# GP8102STEST.net
KiCad netlist of a schematic drawn in Altium Designer
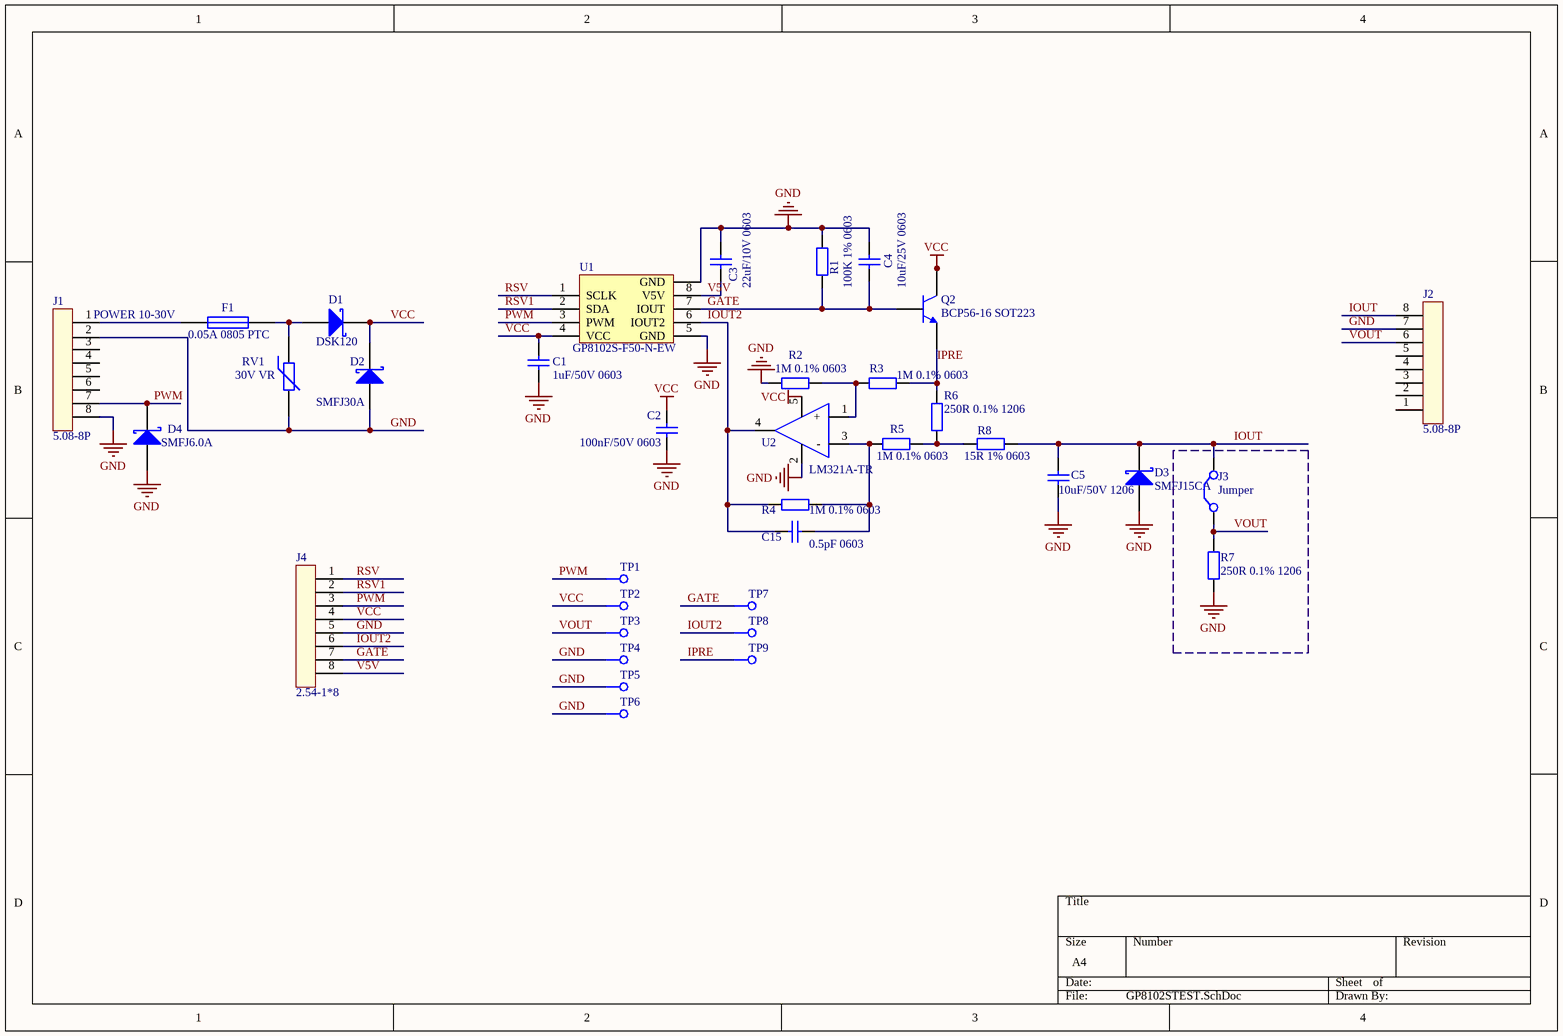
[diagram p0: GP8102STEST.SchDoc]

(export (version "E")
  (design (tool "Eeschema 10.0.6"))
  (components
    (comp (ref "C1")
      (value "1uF/50V 0603")
      (footprint "CAP_0603")
      (fields (field (name "PUBLISHER") "Altium Limited"))
      (libsource (lib "Miscellaneous Devices") (part "Cap"))
    )
    (comp (ref "C2")
      (value "100nF/50V 0603")
      (footprint "CAP_0603")
      (fields (field (name "PUBLISHER") "Altium Limited"))
      (libsource (lib "Miscellaneous Devices") (part "Cap"))
    )
    (comp (ref "C3")
      (value "22uF/10V 0603")
      (footprint "CAP_0603")
      (fields (field (name "PUBLISHER") "Altium Limited"))
      (libsource (lib "Miscellaneous Devices") (part "Cap"))
    )
    (comp (ref "C4")
      (value "10uF/25V 0603")
      (footprint "CAP_0603")
      (fields (field (name "PUBLISHER") "Altium Limited"))
      (libsource (lib "Miscellaneous Devices") (part "Cap"))
    )
    (comp (ref "C5")
      (value "10uF/50V 1206")
      (footprint "CAP_1206")
      (fields (field (name "Comment") "10nF/50V 1206") (field (name "PUBLISHER") "Altium Limited"))
      (libsource (lib "Miscellaneous Devices") (part "Cap"))
    )
    (comp (ref "C15")
      (value "0.5pF 0603")
      (footprint "CAP_0603")
      (description "1pF 0603")
      (fields (field (name "PUBLISHER") "Altium Limited"))
      (libsource (lib "Miscellaneous Devices") (part "Cap"))
    )
    (comp (ref "D1")
      (value "DSK120")
      (footprint "SODFL370X120-2N")
      (fields (field (name "PUBLISHER") "Altium Limited"))
      (libsource (lib "Miscellaneous Devices") (part "D Schottky"))
    )
    (comp (ref "D2")
      (value "SMFJ30A")
      (footprint "SODFL370X120-2N")
      (fields (field (name "PUBLISHER") "Altium Limited"))
      (libsource (lib "Miscellaneous Devices") (part "D Schottky"))
    )
    (comp (ref "D3")
      (value "SMFJ15CA")
      (footprint "SODFL370X120-2N")
      (fields (field (name "PUBLISHER") "Altium Limited"))
      (libsource (lib "Miscellaneous Devices") (part "D Schottky"))
    )
    (comp (ref "D4")
      (value "SMFJ6.0A")
      (footprint "SODFL370X120-2N")
      (fields (field (name "PUBLISHER") "Altium Limited"))
      (libsource (lib "Miscellaneous Devices") (part "D Schottky"))
    )
    (comp (ref "F1")
      (value "0.05A 0805 PTC")
      (footprint "RES_0805")
      (fields (field (name "PUBLISHER") "Altium Limited"))
      (libsource (lib "Miscellaneous Devices") (part "Fuse 1"))
    )
    (comp (ref "J1") (value "5.08-8P") (footprint "5.08-8P") (libsource (lib "SFM") (part "5.08-8P")))
    (comp (ref "J2") (value "5.08-8P") (footprint "5.08-8P") (libsource (lib "") (part "5.08-8P_2")))
    (comp (ref "J3")
      (value "Jumper")
      (footprint "2.54-1*2")
      (description "Jumper Wire")
      (fields (field (name "PUBLISHER") "Altium Limited"))
      (libsource (lib "Miscellaneous Devices") (part "Jumper"))
    )
    (comp (ref "J4")
      (value "2.54-1*8")
      (footprint "2.54-1*8")
      (description "5.08-8P")
      (libsource (lib "") (part "5.08-8P_1"))
    )
    (comp (ref "Q2")
      (value "BCP56-16 SOT223")
      (footprint "NPN_SOT223")
      (libsource (lib "SFM") (part "NPN_SOT223"))
    )
    (comp (ref "R1")
      (value "100K 1% 0603")
      (footprint "RES_0603")
      (fields (field (name "PUBLISHER") "Altium Limited"))
      (libsource (lib "") (part "Res2_1"))
    )
    (comp (ref "R2")
      (value "1M 0.1% 0603")
      (footprint "RES_0603")
      (description "1M 0603")
      (fields (field (name "PUBLISHER") "Altium Limited"))
      (libsource (lib "Miscellaneous Devices") (part "Res2"))
    )
    (comp (ref "R3")
      (value "1M 0.1% 0603")
      (footprint "RES_0603")
      (description "1M 0603")
      (fields (field (name "PUBLISHER") "Altium Limited"))
      (libsource (lib "Miscellaneous Devices") (part "Res2"))
    )
    (comp (ref "R4")
      (value "1M 0.1% 0603")
      (footprint "RES_0603")
      (description "1M 0603")
      (fields (field (name "PUBLISHER") "Altium Limited"))
      (libsource (lib "") (part "Res2_3"))
    )
    (comp (ref "R5")
      (value "1M 0.1% 0603")
      (footprint "RES_0603")
      (description "1M 0603")
      (fields (field (name "PUBLISHER") "Altium Limited"))
      (libsource (lib "Miscellaneous Devices") (part "Res2"))
    )
    (comp (ref "R6")
      (value "250R 0.1% 1206")
      (footprint "RES_1206")
      (fields (field (name "PUBLISHER") "Altium Limited"))
      (libsource (lib "") (part "Res2_2"))
    )
    (comp (ref "R7")
      (value "250R 0.1% 1206")
      (footprint "RES_1206")
      (fields (field (name "PUBLISHER") "Altium Limited"))
      (libsource (lib "") (part "Res2_2"))
    )
    (comp (ref "R8")
      (value "15R 1% 0603")
      (footprint "RES_0603")
      (description "1M 0603")
      (fields (field (name "PUBLISHER") "Altium Limited"))
      (libsource (lib "") (part "Res2_3"))
    )
    (comp (ref "RV1")
      (value "30V VR")
      (footprint "RES_0805")
      (fields (field (name "PUBLISHER") "Altium Limited"))
      (libsource (lib "Miscellaneous Devices") (part "Res Varistor"))
    )
    (comp (ref "TP1")
      (value "PWM")
      (footprint "Hole_Test")
      (description "TP")
      (libsource (lib "WXL_Integrated_Library") (part "Hole"))
    )
    (comp (ref "TP2")
      (value "VCC")
      (footprint "Hole_Test")
      (description "TP")
      (libsource (lib "WXL_Integrated_Library") (part "Hole"))
    )
    (comp (ref "TP3")
      (value "VOUT")
      (footprint "Hole_Test")
      (description "TP")
      (libsource (lib "WXL_Integrated_Library") (part "Hole"))
    )
    (comp (ref "TP4")
      (value "GND")
      (footprint "Hole_Test")
      (description "TP")
      (libsource (lib "WXL_Integrated_Library") (part "Hole"))
    )
    (comp (ref "TP5")
      (value "GND")
      (footprint "Hole_Test")
      (description "TP")
      (libsource (lib "WXL_Integrated_Library") (part "Hole"))
    )
    (comp (ref "TP6")
      (value "GND")
      (footprint "Hole_Test")
      (description "TP")
      (libsource (lib "WXL_Integrated_Library") (part "Hole"))
    )
    (comp (ref "TP7")
      (value "IOUT_7")
      (footprint "Hole_Test")
      (description "TP")
      (libsource (lib "WXL_Integrated_Library") (part "Hole"))
    )
    (comp (ref "TP8")
      (value "IOUT2")
      (footprint "Hole_Test")
      (description "TP")
      (libsource (lib "WXL_Integrated_Library") (part "Hole"))
    )
    (comp (ref "TP9")
      (value "IPRE")
      (footprint "Hole_Test")
      (description "TP")
      (libsource (lib "WXL_Integrated_Library") (part "Hole"))
    )
    (comp (ref "U1") (value "GP8102S-F50-N-EW") (footprint "ESOIC-8") (libsource (lib "SFM") (part "GP810x")))
    (comp (ref "U2")
      (value "LM321A-TR")
      (footprint "SOT23-5")
      (description "LM321 SOT23-5")
      (libsource (lib "SFM") (part "LM321"))
    )
  )
  (nets
    (net (code "1") (name "/GATE") (class "Default")
      (node (ref "C4") (pin "1") (pinfunction "1_1") (pintype "passive"))
      (node (ref "J4") (pin "7") (pintype "passive"))
      (node (ref "Q2") (pin "1") (pintype "passive"))
      (node (ref "R1") (pin "2") (pinfunction "2_2") (pintype "passive"))
      (node (ref "TP7") (pin "1") (pinfunction "SHell_1") (pintype "passive"))
      (node (ref "U1") (pin "7") (pinfunction "IOUT_7") (pintype "passive"))
    )
    (net (code "2") (name "/IOUT") (class "Default")
      (node (ref "C5") (pin "2") (pinfunction "2_2") (pintype "passive"))
      (node (ref "D3") (pin "2") (pinfunction "K_2") (pintype "passive"))
      (node (ref "J2") (pin "8") (pintype "passive"))
      (node (ref "J3") (pin "2") (pinfunction "C2_2") (pintype "passive"))
      (node (ref "R8") (pin "2") (pinfunction "2_2") (pintype "passive"))
    )
    (net (code "3") (name "/IOUT2") (class "Default")
      (node (ref "C15") (pin "1") (pinfunction "1_1") (pintype "passive"))
      (node (ref "J4") (pin "6") (pintype "passive"))
      (node (ref "R4") (pin "1") (pinfunction "1_1") (pintype "passive"))
      (node (ref "TP8") (pin "1") (pinfunction "SHell_1") (pintype "passive"))
      (node (ref "U1") (pin "6") (pinfunction "IOUT2_6") (pintype "passive"))
      (node (ref "U2") (pin "4") (pinfunction "OUTA_4") (pintype "passive"))
    )
    (net (code "4") (name "/IPRE") (class "Default")
      (node (ref "Q2") (pin "3") (pintype "passive"))
      (node (ref "R3") (pin "1") (pinfunction "1_1") (pintype "passive"))
      (node (ref "R6") (pin "2") (pinfunction "2_2") (pintype "passive"))
      (node (ref "TP9") (pin "1") (pinfunction "SHell_1") (pintype "passive"))
    )
    (net (code "5") (name "/PWM") (class "Default")
      (node (ref "D4") (pin "2") (pinfunction "K_2") (pintype "passive"))
      (node (ref "J1") (pin "7") (pintype "passive"))
      (node (ref "J4") (pin "3") (pintype "passive"))
      (node (ref "TP1") (pin "1") (pinfunction "SHell_1") (pintype "passive"))
      (node (ref "U1") (pin "3") (pinfunction "PWM_3") (pintype "passive"))
    )
    (net (code "6") (name "/RSV") (class "Default")
      (node (ref "J4") (pin "1") (pintype "passive"))
      (node (ref "U1") (pin "1") (pinfunction "SCLK_1") (pintype "passive"))
    )
    (net (code "7") (name "/RSV1") (class "Default")
      (node (ref "J4") (pin "2") (pintype "passive"))
      (node (ref "U1") (pin "2") (pinfunction "SDA_2") (pintype "passive"))
    )
    (net (code "8") (name "/V5V") (class "Default")
      (node (ref "C3") (pin "1") (pinfunction "1_1") (pintype "passive"))
      (node (ref "J4") (pin "8") (pintype "passive"))
      (node (ref "U1") (pin "8") (pinfunction "V5V_8") (pintype "passive"))
    )
    (net (code "9") (name "/VOUT") (class "Default")
      (node (ref "J2") (pin "6") (pintype "passive"))
      (node (ref "J3") (pin "1") (pinfunction "C1_1") (pintype "passive"))
      (node (ref "R7") (pin "2") (pinfunction "2_2") (pintype "passive"))
      (node (ref "TP3") (pin "1") (pinfunction "SHell_1") (pintype "passive"))
    )
    (net (code "10") (name "GND") (class "Default")
      (node (ref "C1") (pin "2") (pinfunction "2_2") (pintype "passive"))
      (node (ref "C2") (pin "2") (pinfunction "2_2") (pintype "passive"))
      (node (ref "C3") (pin "2") (pinfunction "2_2") (pintype "passive"))
      (node (ref "C4") (pin "2") (pinfunction "2_2") (pintype "passive"))
      (node (ref "C5") (pin "1") (pinfunction "1_1") (pintype "passive"))
      (node (ref "D2") (pin "1") (pinfunction "A_1") (pintype "passive"))
      (node (ref "D3") (pin "1") (pinfunction "A_1") (pintype "passive"))
      (node (ref "D4") (pin "1") (pinfunction "A_1") (pintype "passive"))
      (node (ref "J1") (pin "2") (pintype "passive"))
      (node (ref "J1") (pin "8") (pintype "passive"))
      (node (ref "J2") (pin "7") (pintype "passive"))
      (node (ref "J4") (pin "5") (pintype "passive"))
      (node (ref "R1") (pin "1") (pinfunction "1_1") (pintype "passive"))
      (node (ref "R2") (pin "2") (pinfunction "2_2") (pintype "passive"))
      (node (ref "R7") (pin "1") (pinfunction "1_1") (pintype "passive"))
      (node (ref "RV1") (pin "2") (pinfunction "2_2") (pintype "passive"))
      (node (ref "TP4") (pin "1") (pinfunction "SHell_1") (pintype "passive"))
      (node (ref "TP5") (pin "1") (pinfunction "SHell_1") (pintype "passive"))
      (node (ref "TP6") (pin "1") (pinfunction "SHell_1") (pintype "passive"))
      (node (ref "U1") (pin "5") (pinfunction "GND_5") (pintype "passive"))
      (node (ref "U1") (pin "9") (pinfunction "GND_9") (pintype "passive"))
      (node (ref "U2") (pin "2") (pinfunction "VS-_2") (pintype "passive"))
    )
    (net (code "11") (name "Net-(D1-A)") (class "Default")
      (node (ref "D1") (pin "1") (pinfunction "A_1") (pintype "passive"))
      (node (ref "F1") (pin "2") (pinfunction "2_2") (pintype "passive"))
      (node (ref "RV1") (pin "1") (pinfunction "1_1") (pintype "passive"))
    )
    (net (code "12") (name "Net-(F1-Pad1)") (class "Default")
      (node (ref "F1") (pin "1") (pinfunction "1_1") (pintype "passive"))
      (node (ref "J1") (pin "1") (pintype "passive"))
    )
    (net (code "13") (name "Net-(R5-Pad1)") (class "Default")
      (node (ref "R5") (pin "1") (pinfunction "1_1") (pintype "passive"))
      (node (ref "R6") (pin "1") (pinfunction "1_1") (pintype "passive"))
      (node (ref "R8") (pin "1") (pinfunction "1_1") (pintype "passive"))
    )
    (net (code "14") (name "Net-(U2-+)") (class "Default")
      (node (ref "R2") (pin "1") (pinfunction "1_1") (pintype "passive"))
      (node (ref "R3") (pin "2") (pinfunction "2_2") (pintype "passive"))
      (node (ref "U2") (pin "1") (pinfunction "+_1") (pintype "passive"))
    )
    (net (code "15") (name "Net-(U2--)") (class "Default")
      (node (ref "C15") (pin "2") (pinfunction "2_2") (pintype "passive"))
      (node (ref "R4") (pin "2") (pinfunction "2_2") (pintype "passive"))
      (node (ref "R5") (pin "2") (pinfunction "2_2") (pintype "passive"))
      (node (ref "U2") (pin "3") (pinfunction "-_3") (pintype "passive"))
    )
    (net (code "16") (name "VCC") (class "Default")
      (node (ref "C1") (pin "1") (pinfunction "1_1") (pintype "passive"))
      (node (ref "C2") (pin "1") (pinfunction "1_1") (pintype "passive"))
      (node (ref "D1") (pin "2") (pinfunction "K_2") (pintype "passive"))
      (node (ref "D2") (pin "2") (pinfunction "K_2") (pintype "passive"))
      (node (ref "J4") (pin "4") (pintype "passive"))
      (node (ref "Q2") (pin "2") (pintype "passive"))
      (node (ref "Q2") (pin "4") (pintype "passive"))
      (node (ref "TP2") (pin "1") (pinfunction "SHell_1") (pintype "passive"))
      (node (ref "U1") (pin "4") (pinfunction "VCC_4") (pintype "passive"))
      (node (ref "U2") (pin "5") (pinfunction "V+_5") (pintype "passive"))
    )
    (net (code "17") (name "unconnected-(J1-Pad3)") (class "Default")
      (node (ref "J1") (pin "3") (pintype "passive"))
    )
    (net (code "18") (name "unconnected-(J1-Pad4)") (class "Default")
      (node (ref "J1") (pin "4") (pintype "passive"))
    )
    (net (code "19") (name "unconnected-(J1-Pad5)") (class "Default")
      (node (ref "J1") (pin "5") (pintype "passive"))
    )
    (net (code "20") (name "unconnected-(J1-Pad6)") (class "Default")
      (node (ref "J1") (pin "6") (pintype "passive"))
    )
    (net (code "21") (name "unconnected-(J2-Pad1)") (class "Default")
      (node (ref "J2") (pin "1") (pintype "passive"))
    )
    (net (code "22") (name "unconnected-(J2-Pad2)") (class "Default")
      (node (ref "J2") (pin "2") (pintype "passive"))
    )
    (net (code "23") (name "unconnected-(J2-Pad3)") (class "Default")
      (node (ref "J2") (pin "3") (pintype "passive"))
    )
    (net (code "24") (name "unconnected-(J2-Pad4)") (class "Default")
      (node (ref "J2") (pin "4") (pintype "passive"))
    )
    (net (code "25") (name "unconnected-(J2-Pad5)") (class "Default")
      (node (ref "J2") (pin "5") (pintype "passive"))
    )
  )
)
